# SCH_NFC-Card-Athish_2024-10-27.net
KiCad netlist of a schematic drawn in EasyEDA
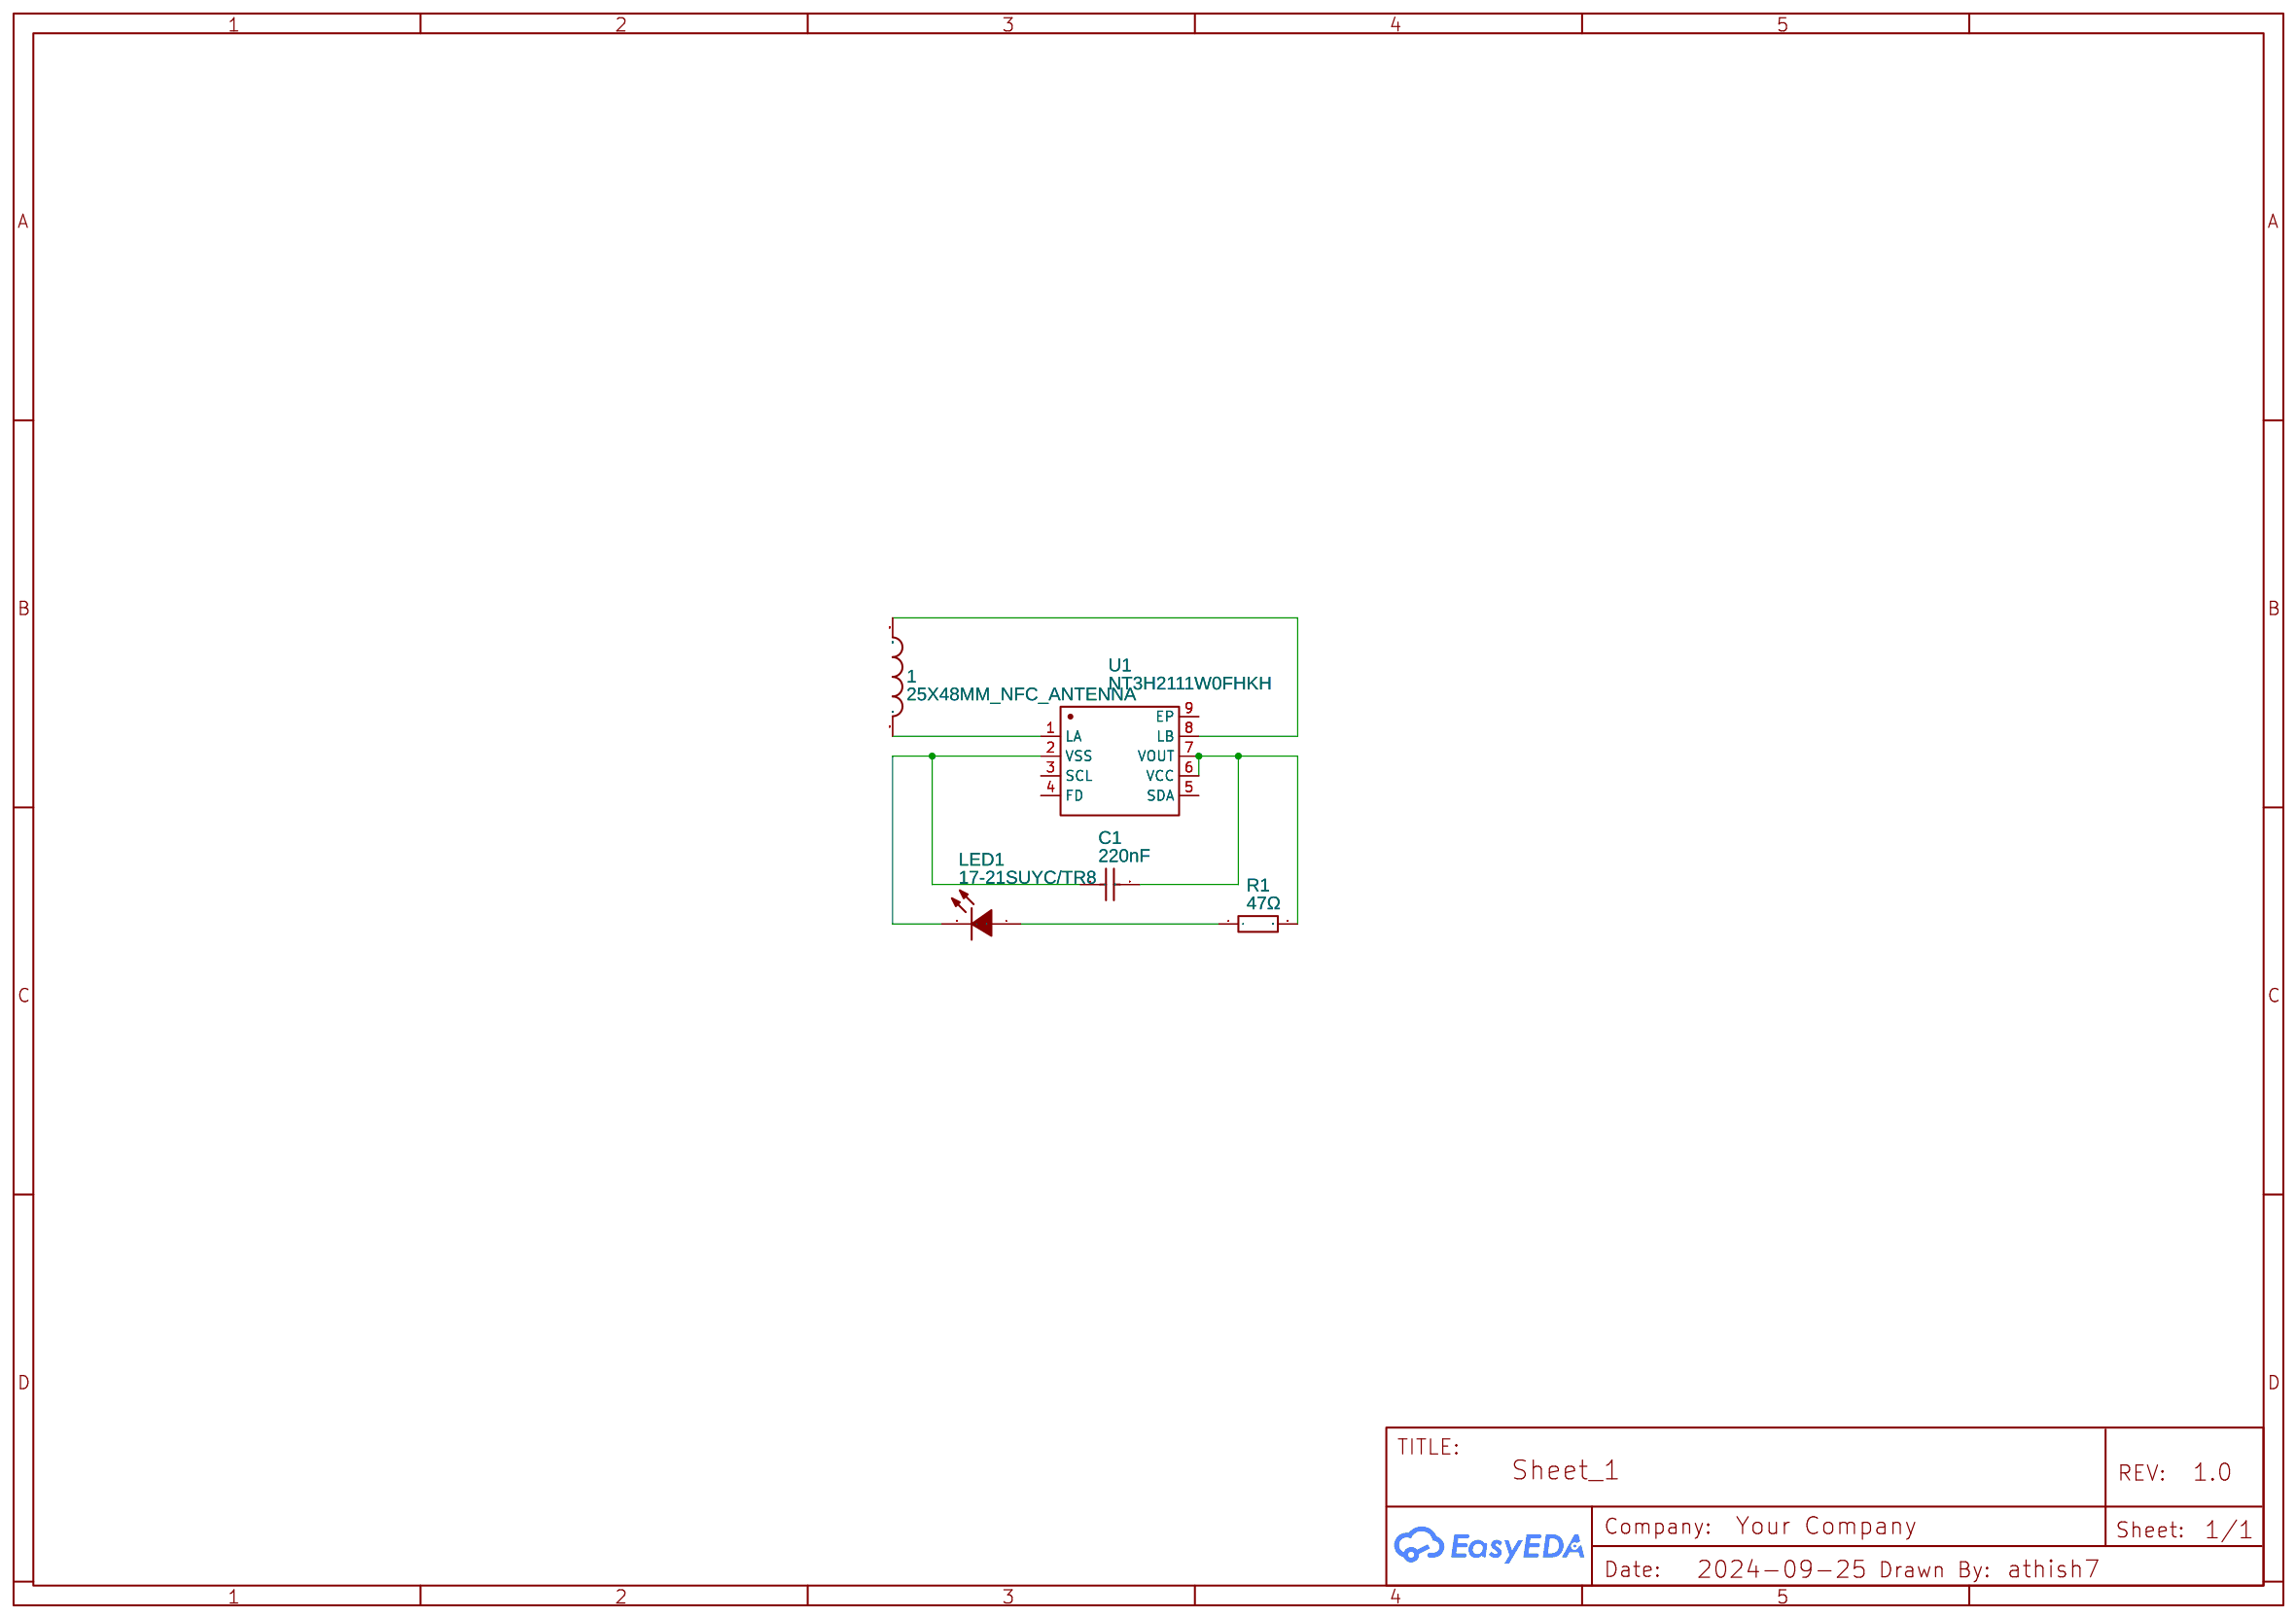
[diagram p0: schematic sheet]

(export (version "E")
  (design (tool "Eeschema 10.0.6"))
  (components
    (comp (ref "1") (value "25X48MM_NFC_ANTENNA") (libsource (lib "") (part "25X48MM_NFC_ANTENNA")))
    (comp (ref "C1")
      (value "220nF")
      (fields
        (field (name "Manufacturer Part") "CL10B224KA8NNNC")
        (field (name "Manufacturer") "SAMSUNG(三星)")
      )
      (libsource (lib "") (part "CL10B224KA8NNNC"))
    )
    (comp (ref "LED1")
      (value "17-21SUYC/TR8")
      (fields (field (name "Manufacturer Part") "KT-0805黄灯") (field (name "Manufacturer") "KENTO"))
      (libsource (lib "") (part "17-21SUYC/TR8"))
    )
    (comp (ref "R1")
      (value "47Ω")
      (fields
        (field (name "Manufacturer Part") "0603WAF470JT5E")
        (field (name "Manufacturer") "UNI-ROYAL(厚声)")
      )
      (libsource (lib "") (part "0603WAF470JT5E"))
    )
    (comp (ref "U1")
      (value "NT3H2111W0FHKH")
      (fields (field (name "Manufacturer") "NXP(恩智浦)"))
      (libsource (lib "") (part "NT3H2111W0FHKH"))
    )
  )
  (nets
    (net (code "1") (name "Net-(LED1-+)") (class "Default")
      (node (ref "LED1") (pin "1") (pinfunction "+_1") (pintype "unspecified"))
      (node (ref "R1") (pin "1") (pinfunction "1_1") (pintype "input"))
    )
    (net (code "2") (name "Net-(LED1--)") (class "Default")
      (node (ref "C1") (pin "1") (pinfunction "1_1") (pintype "input"))
      (node (ref "LED1") (pin "2") (pinfunction "-_2") (pintype "unspecified"))
      (node (ref "U1") (pin "2") (pinfunction "VSS_2") (pintype "unspecified"))
    )
    (net (code "3") (name "Net-(U1-LA)") (class "Default")
      (node (ref "1") (pin "P$2") (pinfunction "P$2_P$2") (pintype "bidirectional"))
      (node (ref "U1") (pin "1") (pinfunction "LA_1") (pintype "unspecified"))
    )
    (net (code "4") (name "Net-(U1-LB)") (class "Default")
      (node (ref "1") (pin "P$1") (pinfunction "P$1_P$1") (pintype "bidirectional"))
      (node (ref "U1") (pin "8") (pinfunction "LB_8") (pintype "unspecified"))
    )
    (net (code "5") (name "Net-(U1-VCC)") (class "Default")
      (node (ref "C1") (pin "2") (pinfunction "2_2") (pintype "input"))
      (node (ref "R1") (pin "2") (pinfunction "2_2") (pintype "input"))
      (node (ref "U1") (pin "6") (pinfunction "VCC_6") (pintype "unspecified"))
      (node (ref "U1") (pin "7") (pinfunction "VOUT_7") (pintype "unspecified"))
    )
    (net (code "6") (name "unconnected-(U1-EP-Pad9)") (class "Default")
      (node (ref "U1") (pin "9") (pinfunction "EP_9") (pintype "unspecified"))
    )
    (net (code "7") (name "unconnected-(U1-FD-Pad4)") (class "Default")
      (node (ref "U1") (pin "4") (pinfunction "FD_4") (pintype "unspecified"))
    )
    (net (code "8") (name "unconnected-(U1-SCL-Pad3)") (class "Default")
      (node (ref "U1") (pin "3") (pinfunction "SCL_3") (pintype "unspecified"))
    )
    (net (code "9") (name "unconnected-(U1-SDA-Pad5)") (class "Default")
      (node (ref "U1") (pin "5") (pinfunction "SDA_5") (pintype "unspecified"))
    )
  )
)
